# GPSReceiver_Kenwood710_tiny.net
KiCad netlist of a schematic drawn in EAGLE
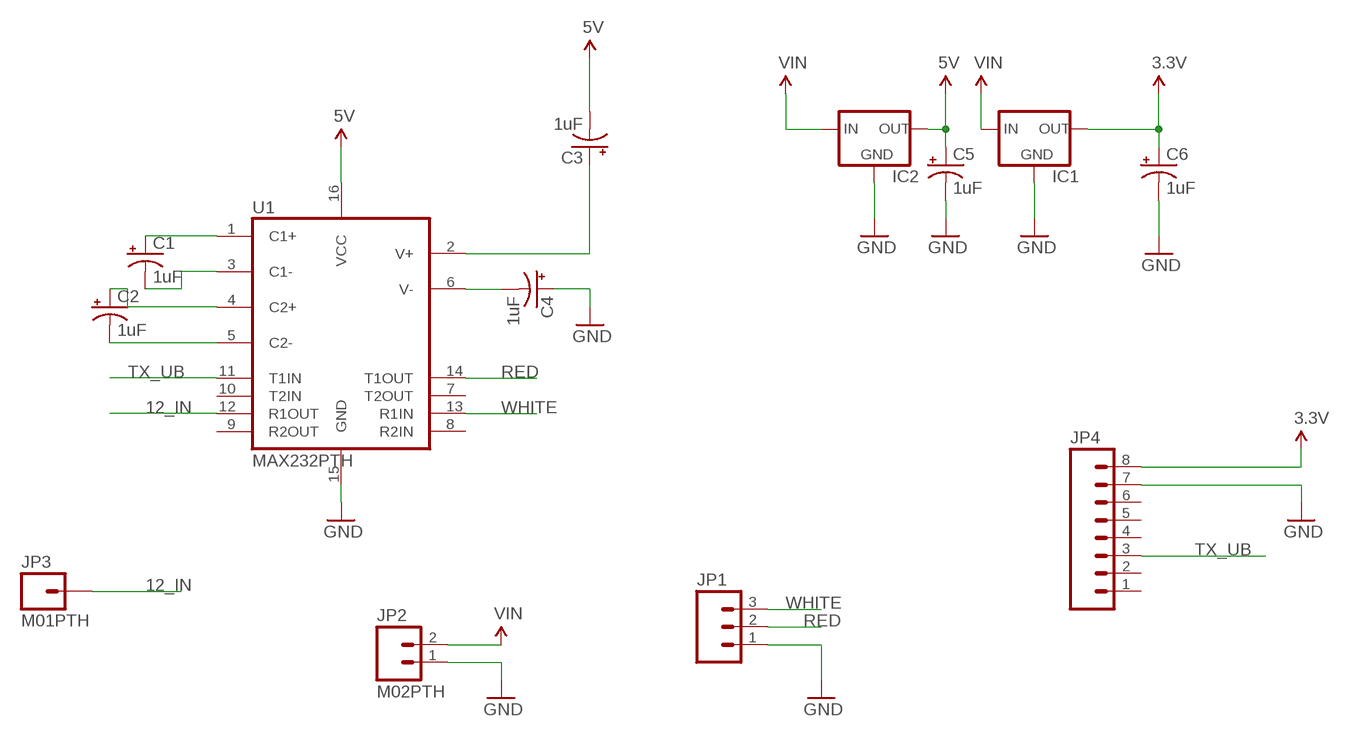
[diagram p0: schematic, sheet 1]

(export (version "E")
  (design (tool "Eeschema 10.0.6"))
  (components
    (comp (ref "C1")
      (value "1uF")
      (footprint "eagle-import:CPOL-RADIAL-10UF-25V")
      (libsource (lib "eagle-import") (part "CAP_POLPTH2"))
    )
    (comp (ref "C2")
      (value "1uF")
      (footprint "eagle-import:CPOL-RADIAL-10UF-25V")
      (libsource (lib "eagle-import") (part "CAP_POLPTH2"))
    )
    (comp (ref "C3")
      (value "1uF")
      (footprint "eagle-import:CPOL-RADIAL-10UF-25V")
      (libsource (lib "eagle-import") (part "CAP_POLPTH2"))
    )
    (comp (ref "C4")
      (value "1uF")
      (footprint "eagle-import:CPOL-RADIAL-10UF-25V")
      (libsource (lib "eagle-import") (part "CAP_POLPTH2"))
    )
    (comp (ref "C5")
      (value "1uF")
      (footprint "eagle-import:CPOL-RADIAL-10UF-25V")
      (libsource (lib "eagle-import") (part "CAP_POLPTH2"))
    )
    (comp (ref "C6")
      (value "1uF")
      (footprint "eagle-import:CPOL-RADIAL-10UF-25V")
      (libsource (lib "eagle-import") (part "CAP_POLPTH2"))
    )
    (comp (ref "IC1")
      (value "V_REG_78XX-TO-220")
      (footprint "eagle-import:TO-220-ALT")
      (libsource (lib "eagle-import") (part "V_REG_78XX-TO-220"))
    )
    (comp (ref "IC2")
      (value "V_REG_78XX-TO-220")
      (footprint "eagle-import:TO-220-ALT")
      (libsource (lib "eagle-import") (part "V_REG_78XX-TO-220"))
    )
    (comp (ref "JP1")
      (value "M03PTH")
      (footprint "eagle-import:1X03")
      (libsource (lib "eagle-import") (part "M03PTH"))
    )
    (comp (ref "JP2")
      (value "M02PTH")
      (footprint "eagle-import:1X02")
      (libsource (lib "eagle-import") (part "M02PTH"))
    )
    (comp (ref "JP3")
      (value "M01PTH")
      (footprint "eagle-import:1X01")
      (libsource (lib "eagle-import") (part "M01PTH"))
    )
    (comp (ref "JP4")
      (value "M08LOCK")
      (footprint "eagle-import:1X08_LOCK")
      (libsource (lib "eagle-import") (part "M08LOCK"))
    )
    (comp (ref "U1")
      (value "MAX232PTH")
      (footprint "eagle-import:DIL16")
      (libsource (lib "eagle-import") (part "MAX232PTH"))
    )
  )
  (nets
    (net (code "1") (name "/12_IN") (class "Default")
      (node (ref "JP3") (pin "1") (pinfunction "1_1") (pintype "passive"))
      (node (ref "U1") (pin "12") (pinfunction "R1OUT_12") (pintype "output"))
    )
    (net (code "2") (name "/RED") (class "Default")
      (node (ref "JP1") (pin "2") (pinfunction "2_2") (pintype "passive"))
      (node (ref "U1") (pin "14") (pinfunction "T1OUT_14") (pintype "output"))
    )
    (net (code "3") (name "/TX_UB") (class "Default")
      (node (ref "JP4") (pin "3") (pinfunction "3_3") (pintype "passive"))
      (node (ref "U1") (pin "11") (pinfunction "T1IN_11") (pintype "input"))
    )
    (net (code "4") (name "/WHITE") (class "Default")
      (node (ref "JP1") (pin "3") (pinfunction "3_3") (pintype "passive"))
      (node (ref "U1") (pin "13") (pinfunction "R1IN_13") (pintype "input"))
    )
    (net (code "5") (name "3.3V") (class "Default")
      (node (ref "C6") (pin "1") (pinfunction "+_1") (pintype "passive"))
      (node (ref "IC1") (pin "OUT") (pinfunction "OUT_OUT") (pintype "output"))
      (node (ref "JP4") (pin "8") (pinfunction "8_8") (pintype "passive"))
    )
    (net (code "6") (name "5V") (class "Default")
      (node (ref "C3") (pin "2") (pinfunction "-_2") (pintype "passive"))
      (node (ref "C5") (pin "1") (pinfunction "+_1") (pintype "passive"))
      (node (ref "IC2") (pin "OUT") (pinfunction "OUT_OUT") (pintype "output"))
      (node (ref "U1") (pin "16") (pinfunction "VCC_16") (pintype "bidirectional"))
    )
    (net (code "7") (name "GND") (class "Default")
      (node (ref "C4") (pin "1") (pinfunction "+_1") (pintype "passive"))
      (node (ref "C5") (pin "2") (pinfunction "-_2") (pintype "passive"))
      (node (ref "C6") (pin "2") (pinfunction "-_2") (pintype "passive"))
      (node (ref "IC1") (pin "GND") (pinfunction "GND_GND") (pintype "input"))
      (node (ref "IC2") (pin "GND") (pinfunction "GND_GND") (pintype "input"))
      (node (ref "JP1") (pin "1") (pinfunction "1_1") (pintype "passive"))
      (node (ref "JP2") (pin "1") (pinfunction "1_1") (pintype "passive"))
      (node (ref "JP4") (pin "7") (pinfunction "7_7") (pintype "passive"))
      (node (ref "U1") (pin "15") (pinfunction "GND_15") (pintype "bidirectional"))
    )
    (net (code "8") (name "Net-(C1-+)") (class "Default")
      (node (ref "C1") (pin "1") (pinfunction "+_1") (pintype "passive"))
      (node (ref "U1") (pin "1") (pinfunction "C1+_1") (pintype "bidirectional"))
    )
    (net (code "9") (name "Net-(C1--)") (class "Default")
      (node (ref "C1") (pin "2") (pinfunction "-_2") (pintype "passive"))
      (node (ref "U1") (pin "3") (pinfunction "C1-_3") (pintype "bidirectional"))
    )
    (net (code "10") (name "Net-(C2-+)") (class "Default")
      (node (ref "C2") (pin "1") (pinfunction "+_1") (pintype "passive"))
      (node (ref "U1") (pin "4") (pinfunction "C2+_4") (pintype "bidirectional"))
    )
    (net (code "11") (name "Net-(C2--)") (class "Default")
      (node (ref "C2") (pin "2") (pinfunction "-_2") (pintype "passive"))
      (node (ref "U1") (pin "5") (pinfunction "C2-_5") (pintype "bidirectional"))
    )
    (net (code "12") (name "Net-(C3-+)") (class "Default")
      (node (ref "C3") (pin "1") (pinfunction "+_1") (pintype "passive"))
      (node (ref "U1") (pin "2") (pinfunction "V+_2") (pintype "bidirectional"))
    )
    (net (code "13") (name "Net-(C4--)") (class "Default")
      (node (ref "C4") (pin "2") (pinfunction "-_2") (pintype "passive"))
      (node (ref "U1") (pin "6") (pinfunction "V-_6") (pintype "bidirectional"))
    )
    (net (code "14") (name "VIN") (class "Default")
      (node (ref "IC1") (pin "IN") (pinfunction "IN_IN") (pintype "input"))
      (node (ref "IC2") (pin "IN") (pinfunction "IN_IN") (pintype "input"))
      (node (ref "JP2") (pin "2") (pinfunction "2_2") (pintype "passive"))
    )
    (net (code "15") (name "unconnected-(JP4-Pad1)") (class "Default")
      (node (ref "JP4") (pin "1") (pinfunction "1_1") (pintype "passive"))
    )
    (net (code "16") (name "unconnected-(JP4-Pad2)") (class "Default")
      (node (ref "JP4") (pin "2") (pinfunction "2_2") (pintype "passive"))
    )
    (net (code "17") (name "unconnected-(JP4-Pad4)") (class "Default")
      (node (ref "JP4") (pin "4") (pinfunction "4_4") (pintype "passive"))
    )
    (net (code "18") (name "unconnected-(JP4-Pad5)") (class "Default")
      (node (ref "JP4") (pin "5") (pinfunction "5_5") (pintype "passive"))
    )
    (net (code "19") (name "unconnected-(JP4-Pad6)") (class "Default")
      (node (ref "JP4") (pin "6") (pinfunction "6_6") (pintype "passive"))
    )
    (net (code "20") (name "unconnected-(U1-R2IN-Pad8)") (class "Default")
      (node (ref "U1") (pin "8") (pinfunction "R2IN_8") (pintype "input"))
    )
    (net (code "21") (name "unconnected-(U1-R2OUT-Pad9)") (class "Default")
      (node (ref "U1") (pin "9") (pinfunction "R2OUT_9") (pintype "output"))
    )
    (net (code "22") (name "unconnected-(U1-T2IN-Pad10)") (class "Default")
      (node (ref "U1") (pin "10") (pinfunction "T2IN_10") (pintype "input"))
    )
    (net (code "23") (name "unconnected-(U1-T2OUT-Pad7)") (class "Default")
      (node (ref "U1") (pin "7") (pinfunction "T2OUT_7") (pintype "output"))
    )
  )
)
